# clock-distribution.net
KiCad netlist of a schematic drawn in Altium Designer
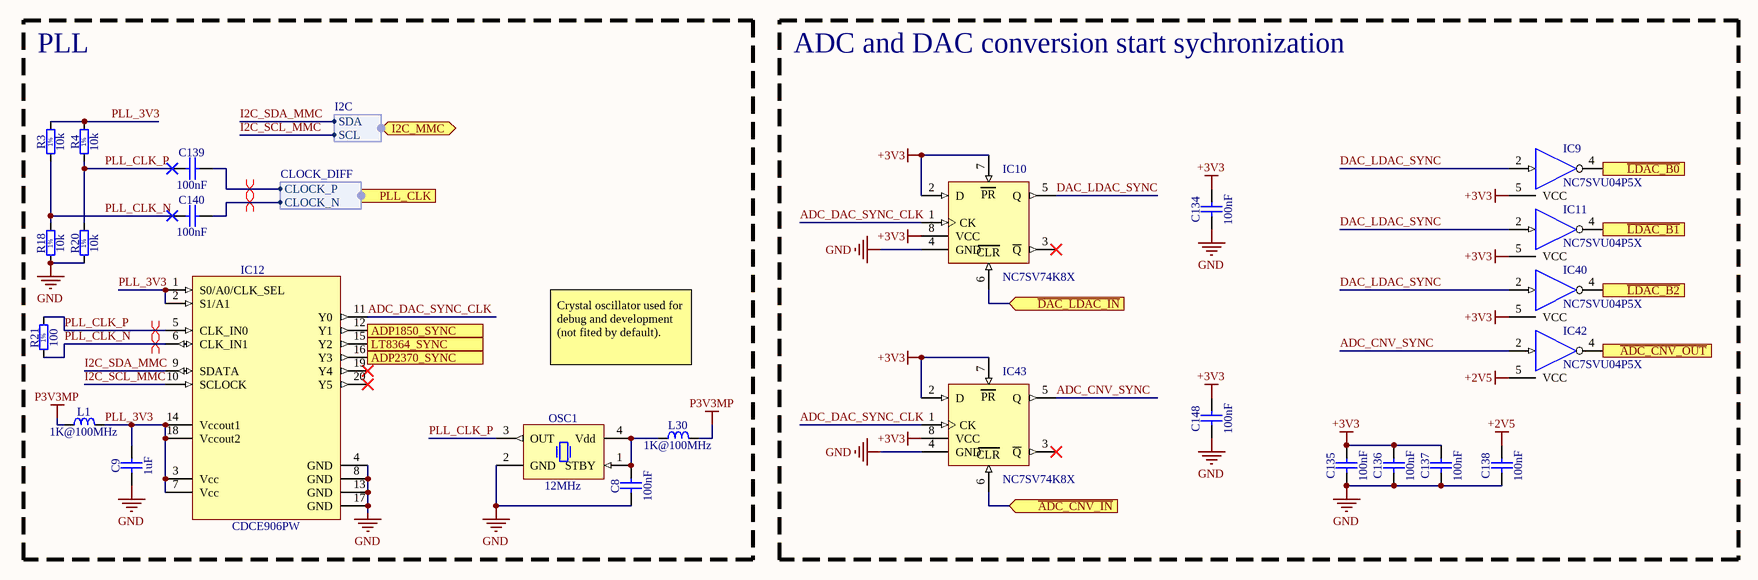
[diagram p0: clock-distribution.SchDoc]

(export (version "E")
  (design (tool "Eeschema 10.0.6"))
  (components
    (comp (ref "C8")
      (value "100nF")
      (footprint "CAPC1005X55N")
      (description "SMD Multilayer Chip Ceramic Capacitor")
      (fields
        (field (name "PART NUMBER") "CC0402_100NF_16V_10%_X7R")
        (field (name "VOLTAGE") "16V")
        (field (name "AUTHOR") "CERN DEM JLC")
      )
      (libsource (lib "Capacitors") (part "Capacitor - non polarized"))
    )
    (comp (ref "C9")
      (value "1uF")
      (footprint "CAPC2012X135N")
      (description "SMD Multilayer Chip Ceramic Capacitor")
      (fields
        (field (name "PART NUMBER") "CC0805_1UF_16V_10%_X7R")
        (field (name "VOLTAGE") "16V")
        (field (name "AUTHOR") "CERN DEM JLC")
      )
      (libsource (lib "Capacitors") (part "Capacitor - non polarized"))
    )
    (comp (ref "C134")
      (value "100nF")
      (footprint "CAPC1005X55N")
      (description "SMD Multilayer Chip Ceramic Capacitor")
      (fields
        (field (name "PART NUMBER") "CC0402_100NF_16V_10%_X7R")
        (field (name "VOLTAGE") "16V")
        (field (name "AUTHOR") "CERN DEM JLC")
      )
      (libsource (lib "Capacitors") (part "Capacitor - non polarized"))
    )
    (comp (ref "C135")
      (value "100nF")
      (footprint "CAPC1005X55N")
      (description "SMD Multilayer Chip Ceramic Capacitor")
      (fields
        (field (name "PART NUMBER") "CC0402_100NF_16V_10%_X7R")
        (field (name "VOLTAGE") "16V")
        (field (name "AUTHOR") "CERN DEM JLC")
      )
      (libsource (lib "Capacitors") (part "Capacitor - non polarized"))
    )
    (comp (ref "C136")
      (value "100nF")
      (footprint "CAPC1005X55N")
      (description "SMD Multilayer Chip Ceramic Capacitor")
      (fields
        (field (name "PART NUMBER") "CC0402_100NF_16V_10%_X7R")
        (field (name "VOLTAGE") "16V")
        (field (name "AUTHOR") "CERN DEM JLC")
      )
      (libsource (lib "Capacitors") (part "Capacitor - non polarized"))
    )
    (comp (ref "C137")
      (value "100nF")
      (footprint "CAPC1005X55N")
      (description "SMD Multilayer Chip Ceramic Capacitor")
      (fields
        (field (name "PART NUMBER") "CC0402_100NF_16V_10%_X7R")
        (field (name "VOLTAGE") "16V")
        (field (name "AUTHOR") "CERN DEM JLC")
      )
      (libsource (lib "Capacitors") (part "Capacitor - non polarized"))
    )
    (comp (ref "C138")
      (value "100nF")
      (footprint "CAPC1005X55N")
      (description "SMD Multilayer Chip Ceramic Capacitor")
      (fields
        (field (name "PART NUMBER") "CC0402_100NF_16V_10%_X7R")
        (field (name "VOLTAGE") "16V")
        (field (name "AUTHOR") "CERN DEM JLC")
      )
      (libsource (lib "Capacitors") (part "Capacitor - non polarized"))
    )
    (comp (ref "C139")
      (value "100nF")
      (footprint "CAPC1005X55N")
      (description "SMD Multilayer Chip Ceramic Capacitor")
      (fields
        (field (name "PART NUMBER") "CC0402_100NF_16V_10%_X7R")
        (field (name "VOLTAGE") "16V")
        (field (name "AUTHOR") "CERN DEM JLC")
      )
      (libsource (lib "Capacitors") (part "Capacitor - non polarized"))
    )
    (comp (ref "C140")
      (value "100nF")
      (footprint "CAPC1005X55N")
      (description "SMD Multilayer Chip Ceramic Capacitor")
      (fields
        (field (name "PART NUMBER") "CC0402_100NF_16V_10%_X7R")
        (field (name "VOLTAGE") "16V")
        (field (name "AUTHOR") "CERN DEM JLC")
      )
      (libsource (lib "Capacitors") (part "Capacitor - non polarized"))
    )
    (comp (ref "C148")
      (value "100nF")
      (footprint "CAPC1005X55N")
      (description "SMD Multilayer Chip Ceramic Capacitor")
      (fields
        (field (name "PART NUMBER") "CC0402_100NF_16V_10%_X7R")
        (field (name "VOLTAGE") "16V")
        (field (name "AUTHOR") "CERN DEM JLC")
      )
      (libsource (lib "Capacitors") (part "Capacitor - non polarized"))
    )
    (comp (ref "IC9")
      (value "NC7SVU04P5X")
      (footprint "SOT65P210X110-5N")
      (description "TinyLogic® ULP-A Unbuffered Inverter")
      (fields (field (name "MANUFACTURER") "FAIRCHILD SEMICONDUCTOR") (field (name "AUTHOR") "LNLS DIG LOS"))
      (libsource (lib "ICs And Semiconductors_LNLS") (part "NC7S04"))
    )
    (comp (ref "IC10")
      (value "NC7SV74K8X")
      (footprint "SOP50P310X90-8N")
      (description "TinyLogic® ULP-A D-Type Flip-Flop with Preset and Clear")
      (fields (field (name "MANUFACTURER") "FAIRCHILD SEMICONDUCTOR") (field (name "AUTHOR") "LNLS DIG LOS"))
      (libsource (lib "ICs And Semiconductors_LNLS") (part "NC7S74"))
    )
    (comp (ref "IC11")
      (value "NC7SVU04P5X")
      (footprint "SOT65P210X110-5N")
      (description "TinyLogic® ULP-A Unbuffered Inverter")
      (fields (field (name "MANUFACTURER") "FAIRCHILD SEMICONDUCTOR") (field (name "AUTHOR") "LNLS DIG LOS"))
      (libsource (lib "ICs And Semiconductors_LNLS") (part "NC7S04"))
    )
    (comp (ref "IC12")
      (value "CDCE906PW")
      (footprint "SOP65P640X120-20N")
      (description "Programmable 3-PLL clock synthesizer / Multiplier / Divider")
      (fields (field (name "MANUFACTURER") "TEXAS INSTRUMENTS") (field (name "AUTHOR") "LNLS DIG LOS"))
      (libsource (lib "ICs And Semiconductors_LNLS") (part "CDCE906"))
    )
    (comp (ref "IC40")
      (value "NC7SVU04P5X")
      (footprint "SOT65P210X110-5N")
      (description "TinyLogic® ULP-A Unbuffered Inverter")
      (fields (field (name "MANUFACTURER") "FAIRCHILD SEMICONDUCTOR") (field (name "AUTHOR") "LNLS DIG LOS"))
      (libsource (lib "ICs And Semiconductors_LNLS") (part "NC7S04"))
    )
    (comp (ref "IC42")
      (value "NC7SVU04P5X")
      (footprint "SOT65P210X110-5N")
      (description "TinyLogic® ULP-A Unbuffered Inverter")
      (fields (field (name "MANUFACTURER") "FAIRCHILD SEMICONDUCTOR") (field (name "AUTHOR") "LNLS DIG LOS"))
      (libsource (lib "ICs And Semiconductors_LNLS") (part "NC7S04"))
    )
    (comp (ref "IC43")
      (value "NC7SV74K8X")
      (footprint "SOP50P310X90-8N")
      (description "TinyLogic® ULP-A D-Type Flip-Flop with Preset and Clear")
      (fields (field (name "MANUFACTURER") "FAIRCHILD SEMICONDUCTOR") (field (name "AUTHOR") "LNLS DIG LOS"))
      (libsource (lib "ICs And Semiconductors_LNLS") (part "NC7S74"))
    )
    (comp (ref "L1")
      (value "1K@100MHz")
      (footprint "INDC1608X95N")
      (description "SMD EMIFIL Suppression Chip Ferrite Bead")
      (fields
        (field (name "PART NUMBER") "IND0603_MURATA_BLM18AG102SN1D")
        (field (name "POWER") "400mA")
        (field (name "AUTHOR") "LNLS DIG GBMB")
      )
      (libsource (lib "Inductors & Transformers_LNLS") (part "Inductor"))
    )
    (comp (ref "L30")
      (value "1K@100MHz")
      (footprint "INDC1608X95N")
      (description "SMD EMIFIL Suppression Chip Ferrite Bead")
      (fields
        (field (name "PART NUMBER") "IND0603_MURATA_BLM18AG102SN1D")
        (field (name "POWER") "400mA")
        (field (name "AUTHOR") "LNLS DIG GBMB")
      )
      (libsource (lib "Inductors & Transformers_LNLS") (part "Inductor"))
    )
    (comp (ref "OSC1")
      (value "12MHz")
      (footprint "XTAL_CONNOR_CS_LNLS")
      (description "3.3V CMOS SMD Crystal Oscillator")
      (fields
        (field (name "PART NUMBER") "ASE-12-D-C-T")
        (field (name "MANUFACTURER") "ABRACON CORPORATION")
        (field (name "AUTHOR") "LNLS DIG LOS")
      )
      (libsource (lib "ICs And Semiconductors_LNLS") (part "Oscillator 1STBY 2GND 3OUT 4Vdd"))
    )
    (comp (ref "R3")
      (value "10k")
      (footprint "RESC1005X40N")
      (description "General Purpose Thick Film Chip Resistor")
      (fields
        (field (name "PART NUMBER") "R0402_10K_1%_0.0625W_100PPM")
        (field (name "POWER") "0.0625W")
        (field (name "AUTHOR") "CERN DEM JLC")
      )
      (libsource (lib "Resistors") (part "Resistor - 1%"))
    )
    (comp (ref "R4")
      (value "10k")
      (footprint "RESC1005X40N")
      (description "General Purpose Thick Film Chip Resistor")
      (fields
        (field (name "PART NUMBER") "R0402_10K_1%_0.0625W_100PPM")
        (field (name "POWER") "0.0625W")
        (field (name "AUTHOR") "CERN DEM JLC")
      )
      (libsource (lib "Resistors") (part "Resistor - 1%"))
    )
    (comp (ref "R18")
      (value "10k")
      (footprint "RESC1005X40N")
      (description "General Purpose Thick Film Chip Resistor")
      (fields
        (field (name "PART NUMBER") "R0402_10K_1%_0.0625W_100PPM")
        (field (name "POWER") "0.0625W")
        (field (name "AUTHOR") "CERN DEM JLC")
      )
      (libsource (lib "Resistors") (part "Resistor - 1%"))
    )
    (comp (ref "R20")
      (value "10k")
      (footprint "RESC1005X40N")
      (description "General Purpose Thick Film Chip Resistor")
      (fields
        (field (name "PART NUMBER") "R0402_10K_1%_0.0625W_100PPM")
        (field (name "POWER") "0.0625W")
        (field (name "AUTHOR") "CERN DEM JLC")
      )
      (libsource (lib "Resistors") (part "Resistor - 1%"))
    )
    (comp (ref "R21")
      (value "100")
      (footprint "RESC1005X40N")
      (description "General Purpose Thick Film Chip Resistor")
      (fields
        (field (name "PART NUMBER") "R0402_100R_1%_0.0625W_100PPM")
        (field (name "POWER") "0.0625W")
        (field (name "AUTHOR") "CERN DEM JLC")
      )
      (libsource (lib "Resistors") (part "Resistor - 1%"))
    )
  )
  (nets
    (net (code "3") (name "+2V5") (class "Default")
      (node (ref "C138") (pin "2") (pinfunction "2_2") (pintype "passive"))
      (node (ref "IC42") (pin "5") (pinfunction "VCC_5") (pintype "power_in"))
    )
    (net (code "4") (name "+3V3") (class "Default")
      (node (ref "C134") (pin "2") (pinfunction "2_2") (pintype "passive"))
      (node (ref "C135") (pin "2") (pinfunction "2_2") (pintype "passive"))
      (node (ref "C136") (pin "2") (pinfunction "2_2") (pintype "passive"))
      (node (ref "C137") (pin "2") (pinfunction "2_2") (pintype "passive"))
      (node (ref "C148") (pin "2") (pinfunction "2_2") (pintype "passive"))
      (node (ref "IC10") (pin "2") (pinfunction "D_2") (pintype "input"))
      (node (ref "IC10") (pin "7") (pinfunction "~{PR}_7") (pintype "input"))
      (node (ref "IC10") (pin "8") (pinfunction "VCC_8") (pintype "power_in"))
      (node (ref "IC11") (pin "5") (pinfunction "VCC_5") (pintype "power_in"))
      (node (ref "IC40") (pin "5") (pinfunction "VCC_5") (pintype "power_in"))
      (node (ref "IC43") (pin "2") (pinfunction "D_2") (pintype "input"))
      (node (ref "IC43") (pin "7") (pinfunction "~{PR}_7") (pintype "input"))
      (node (ref "IC43") (pin "8") (pinfunction "VCC_8") (pintype "power_in"))
      (node (ref "IC9") (pin "5") (pinfunction "VCC_5") (pintype "power_in"))
    )
    (net (code "5") (name "/ADC_CNV_SYNC") (class "Default")
      (node (ref "IC42") (pin "2") (pinfunction "IN_2") (pintype "input"))
      (node (ref "IC43") (pin "5") (pinfunction "Q_5") (pintype "output"))
    )
    (net (code "6") (name "/ADC_DAC_SYNC_CLK") (class "Default")
      (node (ref "IC10") (pin "1") (pinfunction "CK_1") (pintype "input"))
      (node (ref "IC12") (pin "11") (pinfunction "Y0_11") (pintype "output"))
      (node (ref "IC43") (pin "1") (pinfunction "CK_1") (pintype "input"))
    )
    (net (code "7") (name "/ADP1850_SYNC") (class "Default")
      (node (ref "IC12") (pin "12") (pinfunction "Y1_12") (pintype "output"))
    )
    (net (code "8") (name "/ADP2370_SYNC") (class "Default")
      (node (ref "IC12") (pin "16") (pinfunction "Y3_16") (pintype "output"))
    )
    (net (code "9") (name "/CLOCK_N") (class "Default")
      (node (ref "C140") (pin "2") (pinfunction "2_2") (pintype "passive"))
    )
    (net (code "10") (name "/CLOCK_P") (class "Default")
      (node (ref "C139") (pin "2") (pinfunction "2_2") (pintype "passive"))
    )
    (net (code "11") (name "/DAC_LDAC_SYNC") (class "Default")
      (node (ref "IC10") (pin "5") (pinfunction "Q_5") (pintype "output"))
      (node (ref "IC11") (pin "2") (pinfunction "IN_2") (pintype "input"))
      (node (ref "IC40") (pin "2") (pinfunction "IN_2") (pintype "input"))
      (node (ref "IC9") (pin "2") (pinfunction "IN_2") (pintype "input"))
    )
    (net (code "12") (name "/I2C_SCL_MMC") (class "Default")
      (node (ref "IC12") (pin "10") (pinfunction "SCLOCK_10") (pintype "input"))
    )
    (net (code "13") (name "/I2C_SDA_MMC") (class "Default")
      (node (ref "IC12") (pin "9") (pinfunction "SDATA_9") (pintype "bidirectional"))
    )
    (net (code "14") (name "/LT8364_SYNC") (class "Default")
      (node (ref "IC12") (pin "15") (pinfunction "Y2_15") (pintype "output"))
    )
    (net (code "15") (name "/PLL_3V3") (class "Default")
      (node (ref "C9") (pin "2") (pinfunction "2_2") (pintype "passive"))
      (node (ref "IC12") (pin "1") (pinfunction "S0/A0/CLK_SEL_1") (pintype "input"))
      (node (ref "IC12") (pin "14") (pinfunction "Vccout1_14") (pintype "power_in"))
      (node (ref "IC12") (pin "18") (pinfunction "Vccout2_18") (pintype "power_in"))
      (node (ref "IC12") (pin "2") (pinfunction "S1/A1_2") (pintype "input"))
      (node (ref "IC12") (pin "3") (pinfunction "Vcc_3") (pintype "power_in"))
      (node (ref "IC12") (pin "7") (pinfunction "Vcc_7") (pintype "power_in"))
      (node (ref "L1") (pin "2") (pinfunction "2_2") (pintype "passive"))
      (node (ref "R3") (pin "2") (pinfunction "2_2") (pintype "passive"))
      (node (ref "R4") (pin "2") (pinfunction "2_2") (pintype "passive"))
    )
    (net (code "16") (name "/PLL_CLK_N") (class "Default")
      (node (ref "C140") (pin "1") (pinfunction "1_1") (pintype "passive"))
      (node (ref "IC12") (pin "6") (pinfunction "CLK_IN1_6") (pintype "bidirectional"))
      (node (ref "R18") (pin "2") (pinfunction "2_2") (pintype "passive"))
      (node (ref "R21") (pin "1") (pinfunction "1_1") (pintype "passive"))
      (node (ref "R3") (pin "1") (pinfunction "1_1") (pintype "passive"))
    )
    (net (code "17") (name "/PLL_CLK_P") (class "Default")
      (node (ref "C139") (pin "1") (pinfunction "1_1") (pintype "passive"))
      (node (ref "IC12") (pin "5") (pinfunction "CLK_IN0_5") (pintype "input"))
      (node (ref "OSC1") (pin "3") (pinfunction "OUT_3") (pintype "output"))
      (node (ref "R20") (pin "2") (pinfunction "2_2") (pintype "passive"))
      (node (ref "R21") (pin "2") (pinfunction "2_2") (pintype "passive"))
      (node (ref "R4") (pin "1") (pinfunction "1_1") (pintype "passive"))
    )
    (net (code "20") (name "/~{ADC_CNV_IN}") (class "Default")
      (node (ref "IC43") (pin "6") (pinfunction "~{CLR}_6") (pintype "input"))
    )
    (net (code "21") (name "/~{ADC_CNV_OUT}") (class "Default")
      (node (ref "IC42") (pin "4") (pinfunction "OUT_4") (pintype "open_collector"))
    )
    (net (code "22") (name "/~{DAC_LDAC_IN}") (class "Default")
      (node (ref "IC10") (pin "6") (pinfunction "~{CLR}_6") (pintype "input"))
    )
    (net (code "23") (name "/~{LDAC_B0}") (class "Default")
      (node (ref "IC9") (pin "4") (pinfunction "OUT_4") (pintype "open_collector"))
    )
    (net (code "24") (name "/~{LDAC_B1}") (class "Default")
      (node (ref "IC11") (pin "4") (pinfunction "OUT_4") (pintype "open_collector"))
    )
    (net (code "25") (name "/~{LDAC_B2}") (class "Default")
      (node (ref "IC40") (pin "4") (pinfunction "OUT_4") (pintype "open_collector"))
    )
    (net (code "26") (name "GND") (class "Default")
      (node (ref "C134") (pin "1") (pinfunction "1_1") (pintype "passive"))
      (node (ref "C135") (pin "1") (pinfunction "1_1") (pintype "passive"))
      (node (ref "C136") (pin "1") (pinfunction "1_1") (pintype "passive"))
      (node (ref "C137") (pin "1") (pinfunction "1_1") (pintype "passive"))
      (node (ref "C138") (pin "1") (pinfunction "1_1") (pintype "passive"))
      (node (ref "C148") (pin "1") (pinfunction "1_1") (pintype "passive"))
      (node (ref "C8") (pin "1") (pinfunction "1_1") (pintype "passive"))
      (node (ref "C9") (pin "1") (pinfunction "1_1") (pintype "passive"))
      (node (ref "IC10") (pin "4") (pinfunction "GND_4") (pintype "power_in"))
      (node (ref "IC11") (pin "3") (pinfunction "GND_3") (pintype "power_in"))
      (node (ref "IC12") (pin "13") (pinfunction "GND_13") (pintype "power_in"))
      (node (ref "IC12") (pin "17") (pinfunction "GND_17") (pintype "power_in"))
      (node (ref "IC12") (pin "4") (pinfunction "GND_4") (pintype "power_in"))
      (node (ref "IC12") (pin "8") (pinfunction "GND_8") (pintype "power_in"))
      (node (ref "IC40") (pin "3") (pinfunction "GND_3") (pintype "power_in"))
      (node (ref "IC42") (pin "3") (pinfunction "GND_3") (pintype "power_in"))
      (node (ref "IC43") (pin "4") (pinfunction "GND_4") (pintype "power_in"))
      (node (ref "IC9") (pin "3") (pinfunction "GND_3") (pintype "power_in"))
      (node (ref "OSC1") (pin "2") (pinfunction "GND_2") (pintype "power_in"))
      (node (ref "R18") (pin "1") (pinfunction "1_1") (pintype "passive"))
      (node (ref "R20") (pin "1") (pinfunction "1_1") (pintype "passive"))
    )
    (net (code "27") (name "Net-(OSC1-STBY)") (class "Default")
      (node (ref "C8") (pin "2") (pinfunction "2_2") (pintype "passive"))
      (node (ref "L30") (pin "1") (pinfunction "1_1") (pintype "passive"))
      (node (ref "OSC1") (pin "1") (pinfunction "STBY_1") (pintype "input"))
      (node (ref "OSC1") (pin "4") (pinfunction "Vdd_4") (pintype "power_in"))
    )
    (net (code "28") (name "P3V3MP") (class "Default")
      (node (ref "L1") (pin "1") (pinfunction "1_1") (pintype "passive"))
      (node (ref "L30") (pin "2") (pinfunction "2_2") (pintype "passive"))
    )
    (net (code "29") (name "unconnected-(IC10-~{Q}-Pad3)") (class "Default")
      (node (ref "IC10") (pin "3") (pinfunction "~{Q}_3") (pintype "output+no_connect"))
    )
    (net (code "30") (name "unconnected-(IC12-Y4-Pad19)") (class "Default")
      (node (ref "IC12") (pin "19") (pinfunction "Y4_19") (pintype "output+no_connect"))
    )
    (net (code "31") (name "unconnected-(IC12-Y5-Pad20)") (class "Default")
      (node (ref "IC12") (pin "20") (pinfunction "Y5_20") (pintype "output+no_connect"))
    )
    (net (code "32") (name "unconnected-(IC43-~{Q}-Pad3)") (class "Default")
      (node (ref "IC43") (pin "3") (pinfunction "~{Q}_3") (pintype "output+no_connect"))
    )
  )
)
